# AD_Sensors.net
KiCad netlist of a schematic drawn in Altium Designer
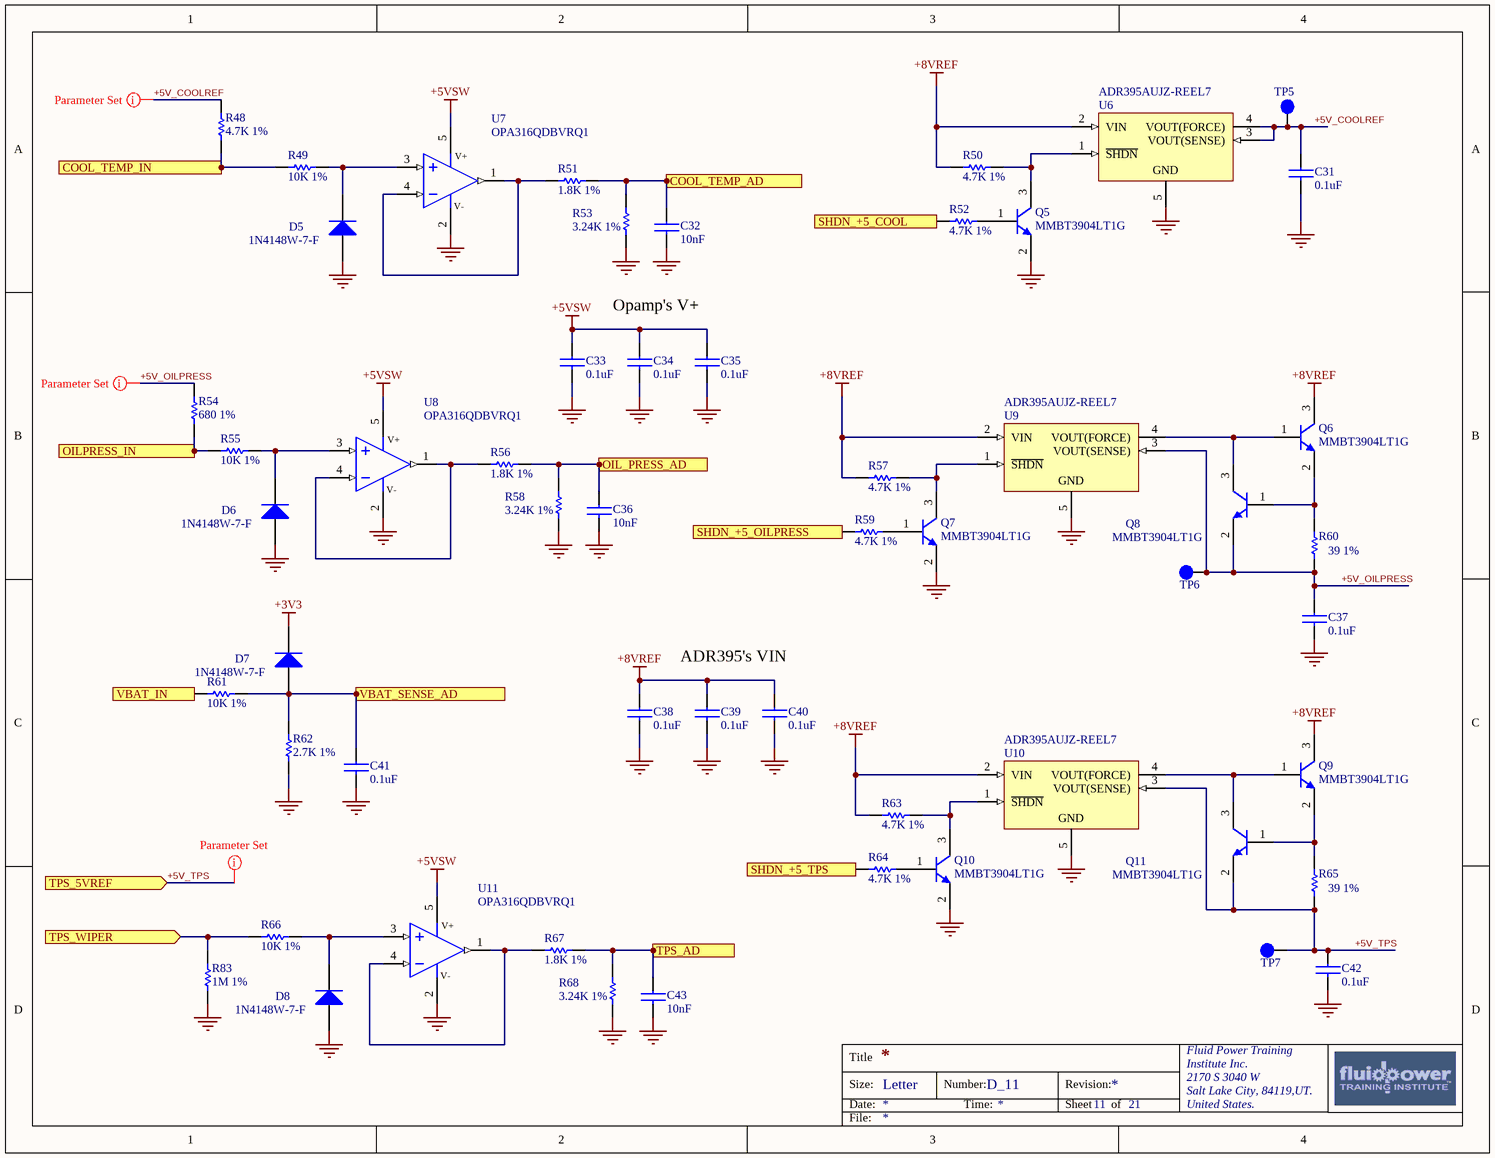
[diagram p0: AD_Sensors.SchDoc]

(export (version "E")
  (design (tool "Eeschema 10.0.6"))
  (components
    (comp (ref "C31")
      (value "0.1uF")
      (footprint "C0805")
      (description "Cap Ceramic 0.1uF 50V X7R 10% SMD 2.0 x 1.2 mm 125 C Paper T/R")
      (fields
        (field (name "MANUFACTURER") "KEMET")
        (field (name "MANUFACTURER PART NUMBER") "C0805C104K5RACTU")
      )
      (libsource (lib "MCx") (part "C0805C104K5RACTU"))
    )
    (comp (ref "C32")
      (value "10nF")
      (footprint "C0805")
      (fields
        (field (name "MANUFACTURER") "Yageo")
        (field (name "MANUFACTURER PART NUMBER") "CC0805KRX7R9BB103")
        (field (name "TOLERANCE") "10%")
      )
      (libsource (lib "MCx") (part "CC0805KRX7R9BB103"))
    )
    (comp (ref "C33")
      (value "0.1uF")
      (footprint "C0805")
      (description "Cap Ceramic 0.1uF 50V X7R 10% SMD 2.0 x 1.2 mm 125 C Paper T/R")
      (fields
        (field (name "MANUFACTURER") "KEMET")
        (field (name "MANUFACTURER PART NUMBER") "C0805C104K5RACTU")
      )
      (libsource (lib "MCx") (part "C0805C104K5RACTU"))
    )
    (comp (ref "C34")
      (value "0.1uF")
      (footprint "C0805")
      (description "Cap Ceramic 0.1uF 50V X7R 10% SMD 2.0 x 1.2 mm 125 C Paper T/R")
      (fields
        (field (name "MANUFACTURER") "KEMET")
        (field (name "MANUFACTURER PART NUMBER") "C0805C104K5RACTU")
      )
      (libsource (lib "MCx") (part "C0805C104K5RACTU"))
    )
    (comp (ref "C35")
      (value "0.1uF")
      (footprint "C0805")
      (description "Cap Ceramic 0.1uF 50V X7R 10% SMD 2.0 x 1.2 mm 125 C Paper T/R")
      (fields
        (field (name "MANUFACTURER") "KEMET")
        (field (name "MANUFACTURER PART NUMBER") "C0805C104K5RACTU")
      )
      (libsource (lib "MCx") (part "C0805C104K5RACTU"))
    )
    (comp (ref "C36")
      (value "10nF")
      (footprint "C0805")
      (fields
        (field (name "MANUFACTURER") "Yageo")
        (field (name "MANUFACTURER PART NUMBER") "CC0805KRX7R9BB103")
        (field (name "TOLERANCE") "10%")
      )
      (libsource (lib "MCx") (part "CC0805KRX7R9BB103"))
    )
    (comp (ref "C37")
      (value "0.1uF")
      (footprint "C0805")
      (description "Cap Ceramic 0.1uF 50V X7R 10% SMD 2.0 x 1.2 mm 125 C Paper T/R")
      (fields
        (field (name "MANUFACTURER") "KEMET")
        (field (name "MANUFACTURER PART NUMBER") "C0805C104K5RACTU")
      )
      (libsource (lib "MCx") (part "C0805C104K5RACTU"))
    )
    (comp (ref "C38")
      (value "0.1uF")
      (footprint "C0805")
      (description "Cap Ceramic 0.1uF 50V X7R 10% SMD 2.0 x 1.2 mm 125 C Paper T/R")
      (fields
        (field (name "MANUFACTURER") "KEMET")
        (field (name "MANUFACTURER PART NUMBER") "C0805C104K5RACTU")
      )
      (libsource (lib "MCx") (part "C0805C104K5RACTU"))
    )
    (comp (ref "C39")
      (value "0.1uF")
      (footprint "C0805")
      (description "Cap Ceramic 0.1uF 50V X7R 10% SMD 2.0 x 1.2 mm 125 C Paper T/R")
      (fields
        (field (name "MANUFACTURER") "KEMET")
        (field (name "MANUFACTURER PART NUMBER") "C0805C104K5RACTU")
      )
      (libsource (lib "MCx") (part "C0805C104K5RACTU"))
    )
    (comp (ref "C40")
      (value "0.1uF")
      (footprint "C0805")
      (description "Cap Ceramic 0.1uF 50V X7R 10% SMD 2.0 x 1.2 mm 125 C Paper T/R")
      (fields
        (field (name "MANUFACTURER") "KEMET")
        (field (name "MANUFACTURER PART NUMBER") "C0805C104K5RACTU")
      )
      (libsource (lib "MCx") (part "C0805C104K5RACTU"))
    )
    (comp (ref "C41")
      (value "0.1uF")
      (footprint "C0805")
      (description "Cap Ceramic 0.1uF 50V X7R 10% SMD 2.0 x 1.2 mm 125 C Paper T/R")
      (fields
        (field (name "MANUFACTURER") "KEMET")
        (field (name "MANUFACTURER PART NUMBER") "C0805C104K5RACTU")
      )
      (libsource (lib "MCx") (part "C0805C104K5RACTU"))
    )
    (comp (ref "C42")
      (value "0.1uF")
      (footprint "C0805")
      (description "Cap Ceramic 0.1uF 50V X7R 10% SMD 2.0 x 1.2 mm 125 C Paper T/R")
      (fields
        (field (name "MANUFACTURER") "KEMET")
        (field (name "MANUFACTURER PART NUMBER") "C0805C104K5RACTU")
      )
      (libsource (lib "MCx") (part "C0805C104K5RACTU"))
    )
    (comp (ref "C43")
      (value "10nF")
      (footprint "C0805")
      (fields
        (field (name "MANUFACTURER") "Yageo")
        (field (name "MANUFACTURER PART NUMBER") "CC0805KRX7R9BB103")
        (field (name "TOLERANCE") "10%")
      )
      (libsource (lib "MCx") (part "CC0805KRX7R9BB103"))
    )
    (comp (ref "D5")
      (value "1N4148W-7-F")
      (footprint "MC1:DIOD-SOD123-2_V")
      (description "DIODE GEN PURP 100V 300MA SOD123")
      (fields (field (name "MANUFACTURER") "Diodes") (field (name "VOLTAGE") "100V"))
      (libsource (lib "MC1") (part "1N4148W-7-F"))
    )
    (comp (ref "D6")
      (value "1N4148W-7-F")
      (footprint "MC1:DIOD-SOD123-2_V")
      (description "DIODE GEN PURP 100V 300MA SOD123")
      (fields (field (name "MANUFACTURER") "Diodes") (field (name "VOLTAGE") "100V"))
      (libsource (lib "MC1") (part "1N4148W-7-F"))
    )
    (comp (ref "D7")
      (value "1N4148W-7-F")
      (footprint "MC1:DIOD-SOD123-2_V")
      (description "DIODE GEN PURP 100V 300MA SOD123")
      (fields (field (name "MANUFACTURER") "Diodes") (field (name "VOLTAGE") "100V"))
      (libsource (lib "MC1") (part "1N4148W-7-F"))
    )
    (comp (ref "D8")
      (value "1N4148W-7-F")
      (footprint "MC1:DIOD-SOD123-2_V")
      (description "DIODE GEN PURP 100V 300MA SOD123")
      (fields (field (name "MANUFACTURER") "Diodes") (field (name "VOLTAGE") "100V"))
      (libsource (lib "MC1") (part "1N4148W-7-F"))
    )
    (comp (ref "Q5")
      (value "MMBT3904LT1G")
      (footprint "MC1:ONSC-SOT-23-3-318-08_V")
      (description "ON Semi MMBT3904LT1G NPN Bipolar Transistor, 0.2 A, 40 V, 3-Pin SOT-23")
      (fields (field (name "MANUFACTURER") "ON Semiconductor"))
      (libsource (lib "MC1") (part "MMBT3904LT1G"))
    )
    (comp (ref "Q6")
      (value "MMBT3904LT1G")
      (footprint "MC1:ONSC-SOT-23-3-318-08_V")
      (description "ON Semi MMBT3904LT1G NPN Bipolar Transistor, 0.2 A, 40 V, 3-Pin SOT-23")
      (fields (field (name "MANUFACTURER") "ON Semiconductor"))
      (libsource (lib "MC1") (part "MMBT3904LT1G"))
    )
    (comp (ref "Q7")
      (value "MMBT3904LT1G")
      (footprint "MC1:ONSC-SOT-23-3-318-08_V")
      (description "ON Semi MMBT3904LT1G NPN Bipolar Transistor, 0.2 A, 40 V, 3-Pin SOT-23")
      (fields (field (name "MANUFACTURER") "ON Semiconductor"))
      (libsource (lib "MC1") (part "MMBT3904LT1G"))
    )
    (comp (ref "Q8")
      (value "MMBT3904LT1G")
      (footprint "MC1:ONSC-SOT-23-3-318-08_V")
      (description "ON Semi MMBT3904LT1G NPN Bipolar Transistor, 0.2 A, 40 V, 3-Pin SOT-23")
      (fields (field (name "MANUFACTURER") "ON Semiconductor"))
      (libsource (lib "MC1") (part "MMBT3904LT1G"))
    )
    (comp (ref "Q9")
      (value "MMBT3904LT1G")
      (footprint "MC1:ONSC-SOT-23-3-318-08_V")
      (description "ON Semi MMBT3904LT1G NPN Bipolar Transistor, 0.2 A, 40 V, 3-Pin SOT-23")
      (fields (field (name "MANUFACTURER") "ON Semiconductor"))
      (libsource (lib "MC1") (part "MMBT3904LT1G"))
    )
    (comp (ref "Q10")
      (value "MMBT3904LT1G")
      (footprint "MC1:ONSC-SOT-23-3-318-08_V")
      (description "ON Semi MMBT3904LT1G NPN Bipolar Transistor, 0.2 A, 40 V, 3-Pin SOT-23")
      (fields (field (name "MANUFACTURER") "ON Semiconductor"))
      (libsource (lib "MC1") (part "MMBT3904LT1G"))
    )
    (comp (ref "Q11")
      (value "MMBT3904LT1G")
      (footprint "MC1:ONSC-SOT-23-3-318-08_V")
      (description "ON Semi MMBT3904LT1G NPN Bipolar Transistor, 0.2 A, 40 V, 3-Pin SOT-23")
      (fields (field (name "MANUFACTURER") "ON Semiconductor"))
      (libsource (lib "MC1") (part "MMBT3904LT1G"))
    )
    (comp (ref "R48")
      (value "4.7K 1%")
      (footprint "R0805")
      (fields
        (field (name "MANUFACTURER") "Panasonic")
        (field (name "MANUFACTURER PART NUMBER") "ERJ-6ENF4701V")
        (field (name "TOLERANCE") "1%")
      )
      (libsource (lib "MCx") (part "ERJ-6ENF4701V"))
    )
    (comp (ref "R49")
      (value "10K 1%")
      (footprint "R0805")
      (fields
        (field (name "MANUFACTURER") "Vishay")
        (field (name "MANUFACTURER PART NUMBER") "CRCW080510K0FKEA")
        (field (name "TOLERANCE") "1%")
      )
      (libsource (lib "MCx") (part "CRCW080510K0FKEA"))
    )
    (comp (ref "R50")
      (value "4.7K 1%")
      (footprint "R0805")
      (fields
        (field (name "MANUFACTURER") "Panasonic")
        (field (name "MANUFACTURER PART NUMBER") "ERJ-6ENF4701V")
        (field (name "TOLERANCE") "1%")
      )
      (libsource (lib "MCx") (part "ERJ-6ENF4701V"))
    )
    (comp (ref "R51")
      (value "1.8K 1%")
      (footprint "R0805")
      (description "RESISTOR, 0805, 0.125W, 1%, 1K8")
      (fields
        (field (name "MANUFACTURER") "Panasonic")
        (field (name "MANUFACTURER PART NUMBER") "ERJ-6ENF1801V")
      )
      (libsource (lib "MCx") (part "ERJ-6ENF1801V"))
    )
    (comp (ref "R52")
      (value "4.7K 1%")
      (footprint "R0805")
      (fields
        (field (name "MANUFACTURER") "Panasonic")
        (field (name "MANUFACTURER PART NUMBER") "ERJ-6ENF4701V")
        (field (name "TOLERANCE") "1%")
      )
      (libsource (lib "MCx") (part "ERJ-6ENF4701V"))
    )
    (comp (ref "R53")
      (value "3.24K 1%")
      (footprint "R0805")
      (description "VISHAY DRALORIC 	   	CRCW08053K24FKEA 	   	RES, THICK FILM, 3K24, 1%, 125MW, 0805")
      (fields
        (field (name "MANUFACTURER") "Vishay")
        (field (name "MANUFACTURER PART NUMBER") "CRCW08053K24FKEA")
      )
      (libsource (lib "MCx") (part "CRCW08053K24FKEA"))
    )
    (comp (ref "R54")
      (value "680 1%")
      (footprint "R0805")
      (fields
        (field (name "MANUFACTURER") "Panasonic")
        (field (name "MANUFACTURER PART NUMBER") "ERJ6ENF6800V")
        (field (name "TOLERANCE") "1%")
      )
      (libsource (lib "MCx") (part "ERJ6ENF6800V"))
    )
    (comp (ref "R55")
      (value "10K 1%")
      (footprint "R0805")
      (fields
        (field (name "MANUFACTURER") "Vishay")
        (field (name "MANUFACTURER PART NUMBER") "CRCW080510K0FKEA")
        (field (name "TOLERANCE") "1%")
      )
      (libsource (lib "MCx") (part "CRCW080510K0FKEA"))
    )
    (comp (ref "R56")
      (value "1.8K 1%")
      (footprint "R0805")
      (description "RESISTOR, 0805, 0.125W, 1%, 1K8")
      (fields
        (field (name "MANUFACTURER") "Panasonic")
        (field (name "MANUFACTURER PART NUMBER") "ERJ-6ENF1801V")
      )
      (libsource (lib "MCx") (part "ERJ-6ENF1801V"))
    )
    (comp (ref "R57")
      (value "4.7K 1%")
      (footprint "R0805")
      (fields
        (field (name "MANUFACTURER") "Panasonic")
        (field (name "MANUFACTURER PART NUMBER") "ERJ-6ENF4701V")
        (field (name "TOLERANCE") "1%")
      )
      (libsource (lib "MCx") (part "ERJ-6ENF4701V"))
    )
    (comp (ref "R58")
      (value "3.24K 1%")
      (footprint "R0805")
      (description "VISHAY DRALORIC 	   	CRCW08053K24FKEA 	   	RES, THICK FILM, 3K24, 1%, 125MW, 0805")
      (fields
        (field (name "MANUFACTURER") "Vishay")
        (field (name "MANUFACTURER PART NUMBER") "CRCW08053K24FKEA")
      )
      (libsource (lib "MCx") (part "CRCW08053K24FKEA"))
    )
    (comp (ref "R59")
      (value "4.7K 1%")
      (footprint "R0805")
      (fields
        (field (name "MANUFACTURER") "Panasonic")
        (field (name "MANUFACTURER PART NUMBER") "ERJ-6ENF4701V")
        (field (name "TOLERANCE") "1%")
      )
      (libsource (lib "MCx") (part "ERJ-6ENF4701V"))
    )
    (comp (ref "R60")
      (value "39 1%")
      (footprint "R0805")
      (description "Res 39 Ohms;  Pwr-Rtg0.125 W;  Tol 1%;  SMT;  0805;  Tape & Reel")
      (fields
        (field (name "MANUFACTURER") "Panasonic")
        (field (name "MANUFACTURER PART NUMBER") "ERJ-6ENF39R0V")
      )
      (libsource (lib "MCx") (part "ERJ-6ENF39R0V"))
    )
    (comp (ref "R61")
      (value "10K 1%")
      (footprint "R0805")
      (fields
        (field (name "MANUFACTURER") "Vishay")
        (field (name "MANUFACTURER PART NUMBER") "CRCW080510K0FKEA")
        (field (name "TOLERANCE") "1%")
      )
      (libsource (lib "MCx") (part "CRCW080510K0FKEA"))
    )
    (comp (ref "R62")
      (value "2.7K 1%")
      (footprint "R0805")
      (description "RES SMD 2.7K OHM 1% 1/8W 0805")
      (fields
        (field (name "MANUFACTURER") "Yageo")
        (field (name "MANUFACTURER PART NUMBER") "AC0805FR-072K7L")
      )
      (libsource (lib "MCx") (part "AC0805FR-072K7L"))
    )
    (comp (ref "R63")
      (value "4.7K 1%")
      (footprint "R0805")
      (fields
        (field (name "MANUFACTURER") "Panasonic")
        (field (name "MANUFACTURER PART NUMBER") "ERJ-6ENF4701V")
        (field (name "TOLERANCE") "1%")
      )
      (libsource (lib "MCx") (part "ERJ-6ENF4701V"))
    )
    (comp (ref "R64")
      (value "4.7K 1%")
      (footprint "R0805")
      (fields
        (field (name "MANUFACTURER") "Panasonic")
        (field (name "MANUFACTURER PART NUMBER") "ERJ-6ENF4701V")
        (field (name "TOLERANCE") "1%")
      )
      (libsource (lib "MCx") (part "ERJ-6ENF4701V"))
    )
    (comp (ref "R65")
      (value "39 1%")
      (footprint "R0805")
      (description "Res 39 Ohms;  Pwr-Rtg0.125 W;  Tol 1%;  SMT;  0805;  Tape & Reel")
      (fields
        (field (name "MANUFACTURER") "Panasonic")
        (field (name "MANUFACTURER PART NUMBER") "ERJ-6ENF39R0V")
      )
      (libsource (lib "MCx") (part "ERJ-6ENF39R0V"))
    )
    (comp (ref "R66")
      (value "10K 1%")
      (footprint "R0805")
      (fields
        (field (name "MANUFACTURER") "Vishay")
        (field (name "MANUFACTURER PART NUMBER") "CRCW080510K0FKEA")
        (field (name "TOLERANCE") "1%")
      )
      (libsource (lib "MCx") (part "CRCW080510K0FKEA"))
    )
    (comp (ref "R67")
      (value "1.8K 1%")
      (footprint "R0805")
      (description "RESISTOR, 0805, 0.125W, 1%, 1K8")
      (fields
        (field (name "MANUFACTURER") "Panasonic")
        (field (name "MANUFACTURER PART NUMBER") "ERJ-6ENF1801V")
      )
      (libsource (lib "MCx") (part "ERJ-6ENF1801V"))
    )
    (comp (ref "R68")
      (value "3.24K 1%")
      (footprint "R0805")
      (description "VISHAY DRALORIC 	   	CRCW08053K24FKEA 	   	RES, THICK FILM, 3K24, 1%, 125MW, 0805")
      (fields
        (field (name "MANUFACTURER") "Vishay")
        (field (name "MANUFACTURER PART NUMBER") "CRCW08053K24FKEA")
      )
      (libsource (lib "MCx") (part "CRCW08053K24FKEA"))
    )
    (comp (ref "R83")
      (value "1M 1%")
      (footprint "R0805")
      (description "Res Thick Film 0805 1M Ohm 1% 1/8W 100ppm/C Molded SMD Punched Carrier T/R")
      (fields
        (field (name "MANUFACTURER") "Panasonic")
        (field (name "MANUFACTURER PART NUMBER") "ERJ-6ENF1004V")
      )
      (libsource (lib "MCx") (part "ERJ-6ENF1004V"))
    )
    (comp (ref "TP5")
      (value "T")
      (footprint "MC1:TESTPOINTSMD_1x1MM")
      (description "SMD Test Point")
      (libsource (lib "MC1") (part "TestPoint_SMD_1x1"))
    )
    (comp (ref "TP6")
      (value "T")
      (footprint "MC1:TESTPOINTSMD_1x1MM")
      (description "SMD Test Point")
      (libsource (lib "MC1") (part "TestPoint_SMD_1x1"))
    )
    (comp (ref "TP7")
      (value "T")
      (footprint "MC1:TESTPOINTSMD_1x1MM")
      (description "SMD Test Point")
      (libsource (lib "MC1") (part "TestPoint_SMD_1x1"))
    )
    (comp (ref "U6")
      (value "ADR395AUJZ-REEL7")
      (footprint "ADI-UJ-5_M")
      (description "ANALOG DEVICES - ADR395AUJZ-REEL7 - VOLTAGE REF, SERIES, 5V, TSOT-5")
      (fields (field (name "MANUFACTURER") "Analog Devices") (field (name "TOLERANCE") "0.12%"))
      (libsource (lib "MCx") (part "ADR395AUJZ-REEL7"))
    )
    (comp (ref "U7")
      (value "OPA316QDBVRQ1")
      (footprint "DBV0005A_M")
      (description "Op Amp Single Low Power Amplifier R-R I/O ±2.75V/5.5V Automotive 5-Pin SOT-23 T/R")
      (fields (field (name "MANUFACTURER") "Texas Instruments"))
      (libsource (lib "MCx") (part "OPA316QDBVRQ1"))
    )
    (comp (ref "U8")
      (value "OPA316QDBVRQ1")
      (footprint "DBV0005A_M")
      (description "Op Amp Single Low Power Amplifier R-R I/O ±2.75V/5.5V Automotive 5-Pin SOT-23 T/R")
      (fields (field (name "MANUFACTURER") "Texas Instruments"))
      (libsource (lib "MCx") (part "OPA316QDBVRQ1"))
    )
    (comp (ref "U9")
      (value "ADR395AUJZ-REEL7")
      (footprint "ADI-UJ-5_M")
      (description "ANALOG DEVICES - ADR395AUJZ-REEL7 - VOLTAGE REF, SERIES, 5V, TSOT-5")
      (fields (field (name "MANUFACTURER") "Analog Devices") (field (name "TOLERANCE") "0.12%"))
      (libsource (lib "MCx") (part "ADR395AUJZ-REEL7"))
    )
    (comp (ref "U10")
      (value "ADR395AUJZ-REEL7")
      (footprint "ADI-UJ-5_M")
      (description "ANALOG DEVICES - ADR395AUJZ-REEL7 - VOLTAGE REF, SERIES, 5V, TSOT-5")
      (fields (field (name "MANUFACTURER") "Analog Devices") (field (name "TOLERANCE") "0.12%"))
      (libsource (lib "MCx") (part "ADR395AUJZ-REEL7"))
    )
    (comp (ref "U11")
      (value "OPA316QDBVRQ1")
      (footprint "DBV0005A_M")
      (description "Op Amp Single Low Power Amplifier R-R I/O ±2.75V/5.5V Automotive 5-Pin SOT-23 T/R")
      (fields (field (name "MANUFACTURER") "Texas Instruments"))
      (libsource (lib "MCx") (part "OPA316QDBVRQ1"))
    )
  )
  (nets
    (net (code "1") (name "+3V3") (class "Default")
      (node (ref "D7") (pin "2") (pinfunction "K_2") (pintype "passive"))
    )
    (net (code "2") (name "+5VSW") (class "Default")
      (node (ref "C33") (pin "1") (pinfunction "1_1") (pintype "passive"))
      (node (ref "C34") (pin "1") (pinfunction "1_1") (pintype "passive"))
      (node (ref "C35") (pin "1") (pinfunction "1_1") (pintype "passive"))
      (node (ref "U11") (pin "5") (pinfunction "V+_5") (pintype "power_in"))
      (node (ref "U7") (pin "5") (pinfunction "V+_5") (pintype "power_in"))
      (node (ref "U8") (pin "5") (pinfunction "V+_5") (pintype "power_in"))
    )
    (net (code "3") (name "+8VREF") (class "Default")
      (node (ref "C38") (pin "1") (pinfunction "1_1") (pintype "passive"))
      (node (ref "C39") (pin "1") (pinfunction "1_1") (pintype "passive"))
      (node (ref "C40") (pin "1") (pinfunction "1_1") (pintype "passive"))
      (node (ref "Q6") (pin "3") (pinfunction "C_3") (pintype "passive"))
      (node (ref "Q9") (pin "3") (pinfunction "C_3") (pintype "passive"))
      (node (ref "R50") (pin "1") (pinfunction "1_1") (pintype "passive"))
      (node (ref "R57") (pin "1") (pinfunction "1_1") (pintype "passive"))
      (node (ref "R63") (pin "1") (pinfunction "1_1") (pintype "passive"))
      (node (ref "U10") (pin "2") (pinfunction "VIN_2") (pintype "input"))
      (node (ref "U6") (pin "2") (pinfunction "VIN_2") (pintype "input"))
      (node (ref "U9") (pin "2") (pinfunction "VIN_2") (pintype "input"))
    )
    (net (code "4") (name "/+5V_COOLREF") (class "Default")
      (node (ref "C31") (pin "1") (pinfunction "1_1") (pintype "passive"))
      (node (ref "R48") (pin "2") (pinfunction "2_2") (pintype "passive"))
      (node (ref "TP5") (pin "1") (pinfunction "1_1") (pintype "passive"))
      (node (ref "U6") (pin "3") (pinfunction "VOUT(SENSE)_3") (pintype "input"))
      (node (ref "U6") (pin "4") (pinfunction "VOUT(FORCE)_4") (pintype "tri_state"))
    )
    (net (code "5") (name "/+5V_OILPRESS") (class "Default")
      (node (ref "C37") (pin "1") (pinfunction "1_1") (pintype "passive"))
      (node (ref "Q8") (pin "2") (pinfunction "E_2") (pintype "passive"))
      (node (ref "R54") (pin "2") (pinfunction "2_2") (pintype "passive"))
      (node (ref "R60") (pin "1") (pinfunction "1_1") (pintype "passive"))
      (node (ref "TP6") (pin "1") (pinfunction "1_1") (pintype "passive"))
      (node (ref "U9") (pin "3") (pinfunction "VOUT(SENSE)_3") (pintype "input"))
    )
    (net (code "6") (name "/+5V_TPS") (class "Default")
      (node (ref "C42") (pin "1") (pinfunction "1_1") (pintype "passive"))
      (node (ref "Q11") (pin "2") (pinfunction "E_2") (pintype "passive"))
      (node (ref "R65") (pin "1") (pinfunction "1_1") (pintype "passive"))
      (node (ref "TP7") (pin "1") (pinfunction "1_1") (pintype "passive"))
      (node (ref "U10") (pin "3") (pinfunction "VOUT(SENSE)_3") (pintype "input"))
    )
    (net (code "7") (name "/COOL_TEMP_AD") (class "Default")
      (node (ref "C32") (pin "1") (pinfunction "1_1") (pintype "passive"))
      (node (ref "R51") (pin "2") (pinfunction "2_2") (pintype "passive"))
      (node (ref "R53") (pin "2") (pinfunction "2_2") (pintype "passive"))
    )
    (net (code "8") (name "/COOL_TEMP_IN") (class "Default")
      (node (ref "R48") (pin "1") (pinfunction "1_1") (pintype "passive"))
      (node (ref "R49") (pin "1") (pinfunction "1_1") (pintype "passive"))
    )
    (net (code "9") (name "/OILPRESS_IN") (class "Default")
      (node (ref "R54") (pin "1") (pinfunction "1_1") (pintype "passive"))
      (node (ref "R55") (pin "1") (pinfunction "1_1") (pintype "passive"))
    )
    (net (code "10") (name "/OIL_PRESS_AD") (class "Default")
      (node (ref "C36") (pin "1") (pinfunction "1_1") (pintype "passive"))
      (node (ref "R56") (pin "2") (pinfunction "2_2") (pintype "passive"))
      (node (ref "R58") (pin "2") (pinfunction "2_2") (pintype "passive"))
    )
    (net (code "11") (name "/SHDN_+5_COOL") (class "Default")
      (node (ref "R52") (pin "1") (pinfunction "1_1") (pintype "passive"))
    )
    (net (code "12") (name "/SHDN_+5_OILPRESS") (class "Default")
      (node (ref "R59") (pin "1") (pinfunction "1_1") (pintype "passive"))
    )
    (net (code "13") (name "/SHDN_+5_TPS") (class "Default")
      (node (ref "R64") (pin "1") (pinfunction "1_1") (pintype "passive"))
    )
    (net (code "14") (name "/TPS_AD") (class "Default")
      (node (ref "C43") (pin "1") (pinfunction "1_1") (pintype "passive"))
      (node (ref "R67") (pin "2") (pinfunction "2_2") (pintype "passive"))
      (node (ref "R68") (pin "2") (pinfunction "2_2") (pintype "passive"))
    )
    (net (code "15") (name "/TPS_WIPER") (class "Default")
      (node (ref "R66") (pin "1") (pinfunction "1_1") (pintype "passive"))
      (node (ref "R83") (pin "2") (pinfunction "2_2") (pintype "passive"))
    )
    (net (code "16") (name "/VBAT_IN") (class "Default")
      (node (ref "R61") (pin "1") (pinfunction "1_1") (pintype "passive"))
    )
    (net (code "17") (name "/VBAT_SENSE_AD") (class "Default")
      (node (ref "C41") (pin "1") (pinfunction "1_1") (pintype "passive"))
      (node (ref "D7") (pin "1") (pinfunction "A_1") (pintype "passive"))
      (node (ref "R61") (pin "2") (pinfunction "2_2") (pintype "passive"))
      (node (ref "R62") (pin "2") (pinfunction "2_2") (pintype "passive"))
    )
    (net (code "18") (name "GND") (class "Default")
      (node (ref "C31") (pin "2") (pinfunction "2_2") (pintype "passive"))
      (node (ref "C32") (pin "2") (pinfunction "2_2") (pintype "passive"))
      (node (ref "C33") (pin "2") (pinfunction "2_2") (pintype "passive"))
      (node (ref "C34") (pin "2") (pinfunction "2_2") (pintype "passive"))
      (node (ref "C35") (pin "2") (pinfunction "2_2") (pintype "passive"))
      (node (ref "C36") (pin "2") (pinfunction "2_2") (pintype "passive"))
      (node (ref "C37") (pin "2") (pinfunction "2_2") (pintype "passive"))
      (node (ref "C38") (pin "2") (pinfunction "2_2") (pintype "passive"))
      (node (ref "C39") (pin "2") (pinfunction "2_2") (pintype "passive"))
      (node (ref "C40") (pin "2") (pinfunction "2_2") (pintype "passive"))
      (node (ref "C41") (pin "2") (pinfunction "2_2") (pintype "passive"))
      (node (ref "C42") (pin "2") (pinfunction "2_2") (pintype "passive"))
      (node (ref "C43") (pin "2") (pinfunction "2_2") (pintype "passive"))
      (node (ref "D5") (pin "1") (pinfunction "A_1") (pintype "passive"))
      (node (ref "D6") (pin "1") (pinfunction "A_1") (pintype "passive"))
      (node (ref "D8") (pin "1") (pinfunction "A_1") (pintype "passive"))
      (node (ref "Q10") (pin "2") (pinfunction "E_2") (pintype "passive"))
      (node (ref "Q5") (pin "2") (pinfunction "E_2") (pintype "passive"))
      (node (ref "Q7") (pin "2") (pinfunction "E_2") (pintype "passive"))
      (node (ref "R53") (pin "1") (pinfunction "1_1") (pintype "passive"))
      (node (ref "R58") (pin "1") (pinfunction "1_1") (pintype "passive"))
      (node (ref "R62") (pin "1") (pinfunction "1_1") (pintype "passive"))
      (node (ref "R68") (pin "1") (pinfunction "1_1") (pintype "passive"))
      (node (ref "R83") (pin "1") (pinfunction "1_1") (pintype "passive"))
      (node (ref "U10") (pin "5") (pinfunction "GND_5") (pintype "power_in"))
      (node (ref "U11") (pin "2") (pinfunction "V-_2") (pintype "power_in"))
      (node (ref "U6") (pin "5") (pinfunction "GND_5") (pintype "power_in"))
      (node (ref "U7") (pin "2") (pinfunction "V-_2") (pintype "power_in"))
      (node (ref "U8") (pin "2") (pinfunction "V-_2") (pintype "power_in"))
      (node (ref "U9") (pin "5") (pinfunction "GND_5") (pintype "power_in"))
    )
    (net (code "19") (name "Net-(D5-K)") (class "Default")
      (node (ref "D5") (pin "2") (pinfunction "K_2") (pintype "passive"))
      (node (ref "R49") (pin "2") (pinfunction "2_2") (pintype "passive"))
      (node (ref "U7") (pin "3") (pinfunction "IN+_3") (pintype "input"))
    )
    (net (code "20") (name "Net-(D6-K)") (class "Default")
      (node (ref "D6") (pin "2") (pinfunction "K_2") (pintype "passive"))
      (node (ref "R55") (pin "2") (pinfunction "2_2") (pintype "passive"))
      (node (ref "U8") (pin "3") (pinfunction "IN+_3") (pintype "input"))
    )
    (net (code "21") (name "Net-(D8-K)") (class "Default")
      (node (ref "D8") (pin "2") (pinfunction "K_2") (pintype "passive"))
      (node (ref "R66") (pin "2") (pinfunction "2_2") (pintype "passive"))
      (node (ref "U11") (pin "3") (pinfunction "IN+_3") (pintype "input"))
    )
    (net (code "22") (name "Net-(Q5-B)") (class "Default")
      (node (ref "Q5") (pin "1") (pinfunction "B_1") (pintype "passive"))
      (node (ref "R52") (pin "2") (pinfunction "2_2") (pintype "passive"))
    )
    (net (code "23") (name "Net-(Q5-C)") (class "Default")
      (node (ref "Q5") (pin "3") (pinfunction "C_3") (pintype "passive"))
      (node (ref "R50") (pin "2") (pinfunction "2_2") (pintype "passive"))
      (node (ref "U6") (pin "1") (pinfunction "~{SHDN}_1") (pintype "input"))
    )
    (net (code "24") (name "Net-(Q6-B)") (class "Default")
      (node (ref "Q6") (pin "1") (pinfunction "B_1") (pintype "passive"))
      (node (ref "Q8") (pin "3") (pinfunction "C_3") (pintype "passive"))
      (node (ref "U9") (pin "4") (pinfunction "VOUT(FORCE)_4") (pintype "tri_state"))
    )
    (net (code "25") (name "Net-(Q6-E)") (class "Default")
      (node (ref "Q6") (pin "2") (pinfunction "E_2") (pintype "passive"))
      (node (ref "Q8") (pin "1") (pinfunction "B_1") (pintype "passive"))
      (node (ref "R60") (pin "2") (pinfunction "2_2") (pintype "passive"))
    )
    (net (code "26") (name "Net-(Q7-B)") (class "Default")
      (node (ref "Q7") (pin "1") (pinfunction "B_1") (pintype "passive"))
      (node (ref "R59") (pin "2") (pinfunction "2_2") (pintype "passive"))
    )
    (net (code "27") (name "Net-(Q7-C)") (class "Default")
      (node (ref "Q7") (pin "3") (pinfunction "C_3") (pintype "passive"))
      (node (ref "R57") (pin "2") (pinfunction "2_2") (pintype "passive"))
      (node (ref "U9") (pin "1") (pinfunction "~{SHDN}_1") (pintype "input"))
    )
    (net (code "28") (name "Net-(Q10-B)") (class "Default")
      (node (ref "Q10") (pin "1") (pinfunction "B_1") (pintype "passive"))
      (node (ref "R64") (pin "2") (pinfunction "2_2") (pintype "passive"))
    )
    (net (code "29") (name "Net-(Q10-C)") (class "Default")
      (node (ref "Q10") (pin "3") (pinfunction "C_3") (pintype "passive"))
      (node (ref "R63") (pin "2") (pinfunction "2_2") (pintype "passive"))
      (node (ref "U10") (pin "1") (pinfunction "~{SHDN}_1") (pintype "input"))
    )
    (net (code "30") (name "Net-(Q11-B)") (class "Default")
      (node (ref "Q11") (pin "1") (pinfunction "B_1") (pintype "passive"))
      (node (ref "Q9") (pin "2") (pinfunction "E_2") (pintype "passive"))
      (node (ref "R65") (pin "2") (pinfunction "2_2") (pintype "passive"))
    )
    (net (code "31") (name "Net-(Q11-C)") (class "Default")
      (node (ref "Q11") (pin "3") (pinfunction "C_3") (pintype "passive"))
      (node (ref "Q9") (pin "1") (pinfunction "B_1") (pintype "passive"))
      (node (ref "U10") (pin "4") (pinfunction "VOUT(FORCE)_4") (pintype "tri_state"))
    )
    (net (code "32") (name "Net-(U7-IN-)") (class "Default")
      (node (ref "R51") (pin "1") (pinfunction "1_1") (pintype "passive"))
      (node (ref "U7") (pin "1") (pinfunction "OUT_1") (pintype "output"))
      (node (ref "U7") (pin "4") (pinfunction "IN-_4") (pintype "input"))
    )
    (net (code "33") (name "Net-(U8-IN-)") (class "Default")
      (node (ref "R56") (pin "1") (pinfunction "1_1") (pintype "passive"))
      (node (ref "U8") (pin "1") (pinfunction "OUT_1") (pintype "output"))
      (node (ref "U8") (pin "4") (pinfunction "IN-_4") (pintype "input"))
    )
    (net (code "34") (name "Net-(U11-IN-)") (class "Default")
      (node (ref "R67") (pin "1") (pinfunction "1_1") (pintype "passive"))
      (node (ref "U11") (pin "1") (pinfunction "OUT_1") (pintype "output"))
      (node (ref "U11") (pin "4") (pinfunction "IN-_4") (pintype "input"))
    )
  )
)
